# 5V_LINEAR_REGULATOR_BREAKOUT_V00.net
KiCad netlist of a schematic drawn in EAGLE
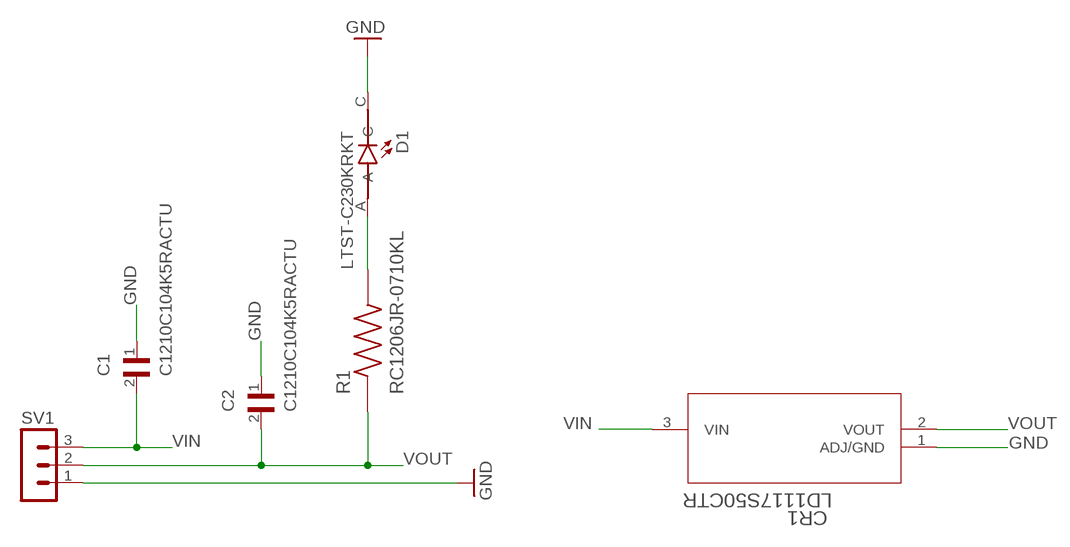
[diagram p0: schematic, sheet 1]

(export (version "E")
  (design (tool "Eeschema 10.0.6"))
  (components
    (comp (ref "C1")
      (value "C1210C104K5RACTU")
      (footprint "eagle-import:CAPC3225X280")
      (fields (field (name "DIGI-KEY_PART_NUMBER") "399-1267-1-ND") (field (name "MF") "KEMET"))
      (libsource (lib "eagle-import") (part "C1210C104K5RACTU"))
    )
    (comp (ref "C2")
      (value "C1210C104K5RACTU")
      (footprint "eagle-import:CAPC3225X280")
      (fields (field (name "DIGI-KEY_PART_NUMBER") "399-1267-1-ND") (field (name "MF") "KEMET"))
      (libsource (lib "eagle-import") (part "C1210C104K5RACTU"))
    )
    (comp (ref "CR1")
      (value "LD1117S50CTR")
      (footprint "eagle-import:SOT-223_STM")
      (libsource (lib "eagle-import") (part "LD1117S50CTR"))
    )
    (comp (ref "D1")
      (value "LTST-C230KRKT")
      (footprint "eagle-import:LEDC3216X110")
      (fields (field (name "DIGI-KEY_PART_NUMBER") "160-1457-1-ND") (field (name "MF") "Lite-On Inc."))
      (libsource (lib "eagle-import") (part "LTST-C230KRKT"))
    )
    (comp (ref "R1")
      (value "RC1206JR-0710KL")
      (footprint "eagle-import:RESC3116X65N")
      (fields (field (name "DIGI-KEY_PART_NUMBER") "311-10KERCT-ND") (field (name "MF") "Yageo"))
      (libsource (lib "eagle-import") (part "RC1206JR-0710KL"))
    )
    (comp (ref "SV1")
      (value "MA03-1")
      (footprint "eagle-import:MA03-1")
      (libsource (lib "eagle-import") (part "MA03-1"))
    )
  )
  (nets
    (net (code "1") (name "/VIN") (class "Default")
      (node (ref "C1") (pin "2") (pinfunction "2_2") (pintype "passive"))
      (node (ref "CR1") (pin "3") (pinfunction "VIN_3") (pintype "power_in"))
      (node (ref "SV1") (pin "3") (pinfunction "3_3") (pintype "passive"))
    )
    (net (code "2") (name "/VOUT") (class "Default")
      (node (ref "C2") (pin "2") (pinfunction "2_2") (pintype "passive"))
      (node (ref "CR1") (pin "2") (pinfunction "VOUT_2") (pintype "power_in"))
      (node (ref "R1") (pin "1") (pinfunction "1_1") (pintype "passive"))
      (node (ref "SV1") (pin "2") (pinfunction "2_2") (pintype "passive"))
    )
    (net (code "3") (name "GND") (class "Default")
      (node (ref "C1") (pin "1") (pinfunction "1_1") (pintype "passive"))
      (node (ref "C2") (pin "1") (pinfunction "1_1") (pintype "passive"))
      (node (ref "CR1") (pin "1") (pinfunction "ADJ/GND_1") (pintype "passive"))
      (node (ref "D1") (pin "C") (pinfunction "C_C") (pintype "passive"))
      (node (ref "SV1") (pin "1") (pinfunction "1_1") (pintype "passive"))
    )
    (net (code "4") (name "Net-(D1-PadA)") (class "Default")
      (node (ref "D1") (pin "A") (pinfunction "A_A") (pintype "passive"))
      (node (ref "R1") (pin "2") (pinfunction "2_2") (pintype "passive"))
    )
  )
)
